# i2c.net
KiCad netlist of a schematic drawn in Altium Designer
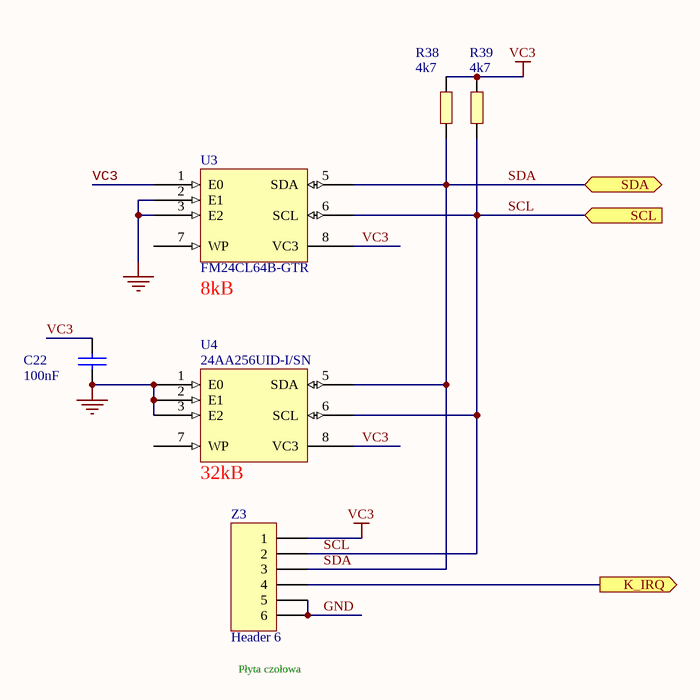
[diagram p0: i2c.SchDoc]

(export (version "E")
  (design (tool "Eeschema 10.0.6"))
  (components
    (comp (ref "C22")
      (value "100nF")
      (footprint "0603C")
      (description "Capacitor")
      (libsource (lib "*") (part "CAP"))
    )
    (comp (ref "R38") (value "4k7") (footprint "0603R") (libsource (lib "*") (part "RES3")))
    (comp (ref "R39") (value "4k7") (footprint "0603R") (libsource (lib "*") (part "RES3")))
    (comp (ref "U3") (value "FM24CL64B-GTR") (footprint "SO8") (libsource (lib "*") (part "AT24C02")))
    (comp (ref "U4") (value "24AA256UID-I/SN") (footprint "SO8") (libsource (lib "*") (part "AT24C02")))
    (comp (ref "Z3")
      (value "Header 6")
      (footprint "UMATCH-6SMD")
      (description "Micro Match 6")
      (fields (field (name "PUBLISHER") "Altium Limited"))
      (libsource (lib "Miscellaneous Connectors") (part "Header 6"))
    )
  )
  (nets
    (net (code "1") (name "/K_IRQ") (class "Default")
      (node (ref "Z3") (pin "4") (pinfunction "4_4") (pintype "passive"))
    )
    (net (code "2") (name "/SCL") (class "Default")
      (node (ref "R39") (pin "2") (pintype "passive"))
      (node (ref "U3") (pin "6") (pinfunction "SCL_6") (pintype "bidirectional"))
      (node (ref "U4") (pin "6") (pinfunction "SCL_6") (pintype "bidirectional"))
      (node (ref "Z3") (pin "2") (pinfunction "2_2") (pintype "passive"))
    )
    (net (code "3") (name "/SDA") (class "Default")
      (node (ref "R38") (pin "2") (pintype "passive"))
      (node (ref "U3") (pin "5") (pinfunction "SDA_5") (pintype "bidirectional"))
      (node (ref "U4") (pin "5") (pinfunction "SDA_5") (pintype "bidirectional"))
      (node (ref "Z3") (pin "3") (pinfunction "3_3") (pintype "passive"))
    )
    (net (code "4") (name "GND") (class "Default")
      (node (ref "C22") (pin "2") (pinfunction "2_2") (pintype "passive"))
      (node (ref "U3") (pin "2") (pinfunction "E1_2") (pintype "input"))
      (node (ref "U3") (pin "3") (pinfunction "E2_3") (pintype "input"))
      (node (ref "U3") (pin "4") (pinfunction "GND_4") (pintype "power_in"))
      (node (ref "U4") (pin "1") (pinfunction "E0_1") (pintype "input"))
      (node (ref "U4") (pin "2") (pinfunction "E1_2") (pintype "input"))
      (node (ref "U4") (pin "3") (pinfunction "E2_3") (pintype "input"))
      (node (ref "U4") (pin "4") (pinfunction "GND_4") (pintype "power_in"))
      (node (ref "Z3") (pin "5") (pinfunction "5_5") (pintype "passive"))
      (node (ref "Z3") (pin "6") (pinfunction "6_6") (pintype "passive"))
    )
    (net (code "5") (name "VC3") (class "Default")
      (node (ref "C22") (pin "1") (pinfunction "1_1") (pintype "passive"))
      (node (ref "R38") (pin "1") (pintype "passive"))
      (node (ref "R39") (pin "1") (pintype "passive"))
      (node (ref "U3") (pin "1") (pinfunction "E0_1") (pintype "input"))
      (node (ref "U3") (pin "8") (pinfunction "VC3_8") (pintype "power_in"))
      (node (ref "U4") (pin "8") (pinfunction "VC3_8") (pintype "power_in"))
      (node (ref "Z3") (pin "1") (pinfunction "1_1") (pintype "passive"))
    )
    (net (code "6") (name "unconnected-(U3-WP-Pad7)") (class "Default")
      (node (ref "U3") (pin "7") (pinfunction "WP_7") (pintype "input"))
    )
    (net (code "7") (name "unconnected-(U4-WP-Pad7)") (class "Default")
      (node (ref "U4") (pin "7") (pinfunction "WP_7") (pintype "input"))
    )
  )
)
